# dip28-tqfp32_mega8.net
KiCad netlist of a schematic drawn in EAGLE
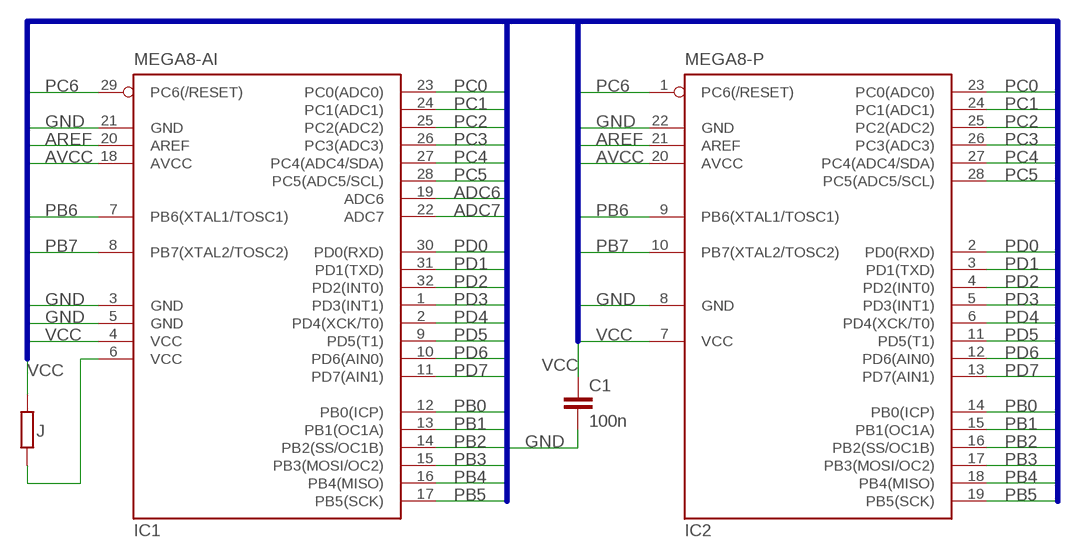
[diagram p0: schematic, sheet 1]

(export (version "E")
  (design (tool "Eeschema 10.0.6"))
  (components
    (comp (ref "C1")
      (value "100n")
      (footprint "eagle-import:C0805")
      (libsource (lib "eagle-import") (part "C-EUC0805"))
    )
    (comp (ref "IC1")
      (value "MEGA8-AI")
      (footprint "eagle-import:TQFP32-08")
      (fields (field (name "MPN") "ATMEGA8-16AU"))
      (libsource (lib "eagle-import") (part "MEGA8-AI"))
    )
    (comp (ref "IC2")
      (value "MEGA8-P")
      (footprint "eagle-import:DIL28-3")
      (libsource (lib "eagle-import") (part "MEGA8-P"))
    )
    (comp (ref "J")
      (value "R-EU_R1206W")
      (footprint "eagle-import:R1206W")
      (libsource (lib "eagle-import") (part "R-EU_R1206W"))
    )
  )
  (nets
    (net (code "1") (name "/ADC6") (class "Default")
      (node (ref "IC1") (pin "19") (pinfunction "ADC6_19") (pintype "bidirectional"))
    )
    (net (code "2") (name "/ADC7") (class "Default")
      (node (ref "IC1") (pin "22") (pinfunction "ADC7_22") (pintype "bidirectional"))
    )
    (net (code "3") (name "/AREF") (class "Default")
      (node (ref "IC1") (pin "20") (pinfunction "AREF_20") (pintype "passive"))
      (node (ref "IC2") (pin "21") (pinfunction "AREF_21") (pintype "passive"))
    )
    (net (code "4") (name "/AVCC") (class "Default")
      (node (ref "IC1") (pin "18") (pinfunction "AVCC_18") (pintype "power_in"))
      (node (ref "IC2") (pin "20") (pinfunction "AVCC_20") (pintype "power_in"))
    )
    (net (code "5") (name "/GND") (class "Default")
      (node (ref "C1") (pin "2") (pinfunction "2_2") (pintype "passive"))
      (node (ref "IC1") (pin "21") (pinfunction "GND_21") (pintype "power_in"))
      (node (ref "IC1") (pin "3") (pinfunction "GND_3") (pintype "power_in"))
      (node (ref "IC1") (pin "5") (pinfunction "GND_5") (pintype "power_in"))
      (node (ref "IC2") (pin "22") (pinfunction "GND_22") (pintype "power_in"))
      (node (ref "IC2") (pin "8") (pinfunction "GND_8") (pintype "power_in"))
    )
    (net (code "6") (name "/PB0") (class "Default")
      (node (ref "IC1") (pin "12") (pinfunction "PB0(ICP)_12") (pintype "bidirectional"))
      (node (ref "IC2") (pin "14") (pinfunction "PB0(ICP)_14") (pintype "bidirectional"))
    )
    (net (code "7") (name "/PB1") (class "Default")
      (node (ref "IC1") (pin "13") (pinfunction "PB1(OC1A)_13") (pintype "bidirectional"))
      (node (ref "IC2") (pin "15") (pinfunction "PB1(OC1A)_15") (pintype "bidirectional"))
    )
    (net (code "8") (name "/PB2") (class "Default")
      (node (ref "IC1") (pin "14") (pinfunction "PB2(SS/OC1B)_14") (pintype "bidirectional"))
      (node (ref "IC2") (pin "16") (pinfunction "PB2(SS/OC1B)_16") (pintype "bidirectional"))
    )
    (net (code "9") (name "/PB3") (class "Default")
      (node (ref "IC1") (pin "15") (pinfunction "PB3(MOSI/OC2)_15") (pintype "bidirectional"))
      (node (ref "IC2") (pin "17") (pinfunction "PB3(MOSI/OC2)_17") (pintype "bidirectional"))
    )
    (net (code "10") (name "/PB4") (class "Default")
      (node (ref "IC1") (pin "16") (pinfunction "PB4(MISO)_16") (pintype "bidirectional"))
      (node (ref "IC2") (pin "18") (pinfunction "PB4(MISO)_18") (pintype "bidirectional"))
    )
    (net (code "11") (name "/PB5") (class "Default")
      (node (ref "IC1") (pin "17") (pinfunction "PB5(SCK)_17") (pintype "bidirectional"))
      (node (ref "IC2") (pin "19") (pinfunction "PB5(SCK)_19") (pintype "bidirectional"))
    )
    (net (code "12") (name "/PB6") (class "Default")
      (node (ref "IC1") (pin "7") (pinfunction "PB6(XTAL1/TOSC1)_7") (pintype "bidirectional"))
      (node (ref "IC2") (pin "9") (pinfunction "PB6(XTAL1/TOSC1)_9") (pintype "bidirectional"))
    )
    (net (code "13") (name "/PB7") (class "Default")
      (node (ref "IC1") (pin "8") (pinfunction "PB7(XTAL2/TOSC2)_8") (pintype "bidirectional"))
      (node (ref "IC2") (pin "10") (pinfunction "PB7(XTAL2/TOSC2)_10") (pintype "bidirectional"))
    )
    (net (code "14") (name "/PC0") (class "Default")
      (node (ref "IC1") (pin "23") (pinfunction "PC0(ADC0)_23") (pintype "bidirectional"))
      (node (ref "IC2") (pin "23") (pinfunction "PC0(ADC0)_23") (pintype "bidirectional"))
    )
    (net (code "15") (name "/PC1") (class "Default")
      (node (ref "IC1") (pin "24") (pinfunction "PC1(ADC1)_24") (pintype "bidirectional"))
      (node (ref "IC2") (pin "24") (pinfunction "PC1(ADC1)_24") (pintype "bidirectional"))
    )
    (net (code "16") (name "/PC2") (class "Default")
      (node (ref "IC1") (pin "25") (pinfunction "PC2(ADC2)_25") (pintype "bidirectional"))
      (node (ref "IC2") (pin "25") (pinfunction "PC2(ADC2)_25") (pintype "bidirectional"))
    )
    (net (code "17") (name "/PC3") (class "Default")
      (node (ref "IC1") (pin "26") (pinfunction "PC3(ADC3)_26") (pintype "bidirectional"))
      (node (ref "IC2") (pin "26") (pinfunction "PC3(ADC3)_26") (pintype "bidirectional"))
    )
    (net (code "18") (name "/PC4") (class "Default")
      (node (ref "IC1") (pin "27") (pinfunction "PC4(ADC4/SDA)_27") (pintype "bidirectional"))
      (node (ref "IC2") (pin "27") (pinfunction "PC4(ADC4/SDA)_27") (pintype "bidirectional"))
    )
    (net (code "19") (name "/PC5") (class "Default")
      (node (ref "IC1") (pin "28") (pinfunction "PC5(ADC5/SCL)_28") (pintype "bidirectional"))
      (node (ref "IC2") (pin "28") (pinfunction "PC5(ADC5/SCL)_28") (pintype "bidirectional"))
    )
    (net (code "20") (name "/PC6") (class "Default")
      (node (ref "IC1") (pin "29") (pinfunction "PC6(/RESET)_29") (pintype "bidirectional"))
      (node (ref "IC2") (pin "1") (pinfunction "PC6(/RESET)_1") (pintype "bidirectional"))
    )
    (net (code "21") (name "/PD0") (class "Default")
      (node (ref "IC1") (pin "30") (pinfunction "PD0(RXD)_30") (pintype "bidirectional"))
      (node (ref "IC2") (pin "2") (pinfunction "PD0(RXD)_2") (pintype "bidirectional"))
    )
    (net (code "22") (name "/PD1") (class "Default")
      (node (ref "IC1") (pin "31") (pinfunction "PD1(TXD)_31") (pintype "bidirectional"))
      (node (ref "IC2") (pin "3") (pinfunction "PD1(TXD)_3") (pintype "bidirectional"))
    )
    (net (code "23") (name "/PD2") (class "Default")
      (node (ref "IC1") (pin "32") (pinfunction "PD2(INT0)_32") (pintype "bidirectional"))
      (node (ref "IC2") (pin "4") (pinfunction "PD2(INT0)_4") (pintype "bidirectional"))
    )
    (net (code "24") (name "/PD3") (class "Default")
      (node (ref "IC1") (pin "1") (pinfunction "PD3(INT1)_1") (pintype "bidirectional"))
      (node (ref "IC2") (pin "5") (pinfunction "PD3(INT1)_5") (pintype "bidirectional"))
    )
    (net (code "25") (name "/PD4") (class "Default")
      (node (ref "IC1") (pin "2") (pinfunction "PD4(XCK/T0)_2") (pintype "bidirectional"))
      (node (ref "IC2") (pin "6") (pinfunction "PD4(XCK/T0)_6") (pintype "bidirectional"))
    )
    (net (code "26") (name "/PD5") (class "Default")
      (node (ref "IC1") (pin "9") (pinfunction "PD5(T1)_9") (pintype "bidirectional"))
      (node (ref "IC2") (pin "11") (pinfunction "PD5(T1)_11") (pintype "bidirectional"))
    )
    (net (code "27") (name "/PD6") (class "Default")
      (node (ref "IC1") (pin "10") (pinfunction "PD6(AIN0)_10") (pintype "bidirectional"))
      (node (ref "IC2") (pin "12") (pinfunction "PD6(AIN0)_12") (pintype "bidirectional"))
    )
    (net (code "28") (name "/PD7") (class "Default")
      (node (ref "IC1") (pin "11") (pinfunction "PD7(AIN1)_11") (pintype "bidirectional"))
      (node (ref "IC2") (pin "13") (pinfunction "PD7(AIN1)_13") (pintype "bidirectional"))
    )
    (net (code "29") (name "/VCC") (class "Default")
      (node (ref "C1") (pin "1") (pinfunction "1_1") (pintype "passive"))
      (node (ref "IC1") (pin "4") (pinfunction "VCC_4") (pintype "power_in"))
      (node (ref "IC2") (pin "7") (pinfunction "VCC_7") (pintype "power_in"))
      (node (ref "J") (pin "2") (pinfunction "2_2") (pintype "passive"))
    )
    (net (code "30") (name "Net-(IC1-VCC-Pad6)") (class "Default")
      (node (ref "IC1") (pin "6") (pinfunction "VCC_6") (pintype "power_in"))
      (node (ref "J") (pin "1") (pinfunction "1_1") (pintype "passive"))
    )
  )
)
